# LATEST_DESIGN.net
KiCad netlist of a schematic drawn in EAGLE
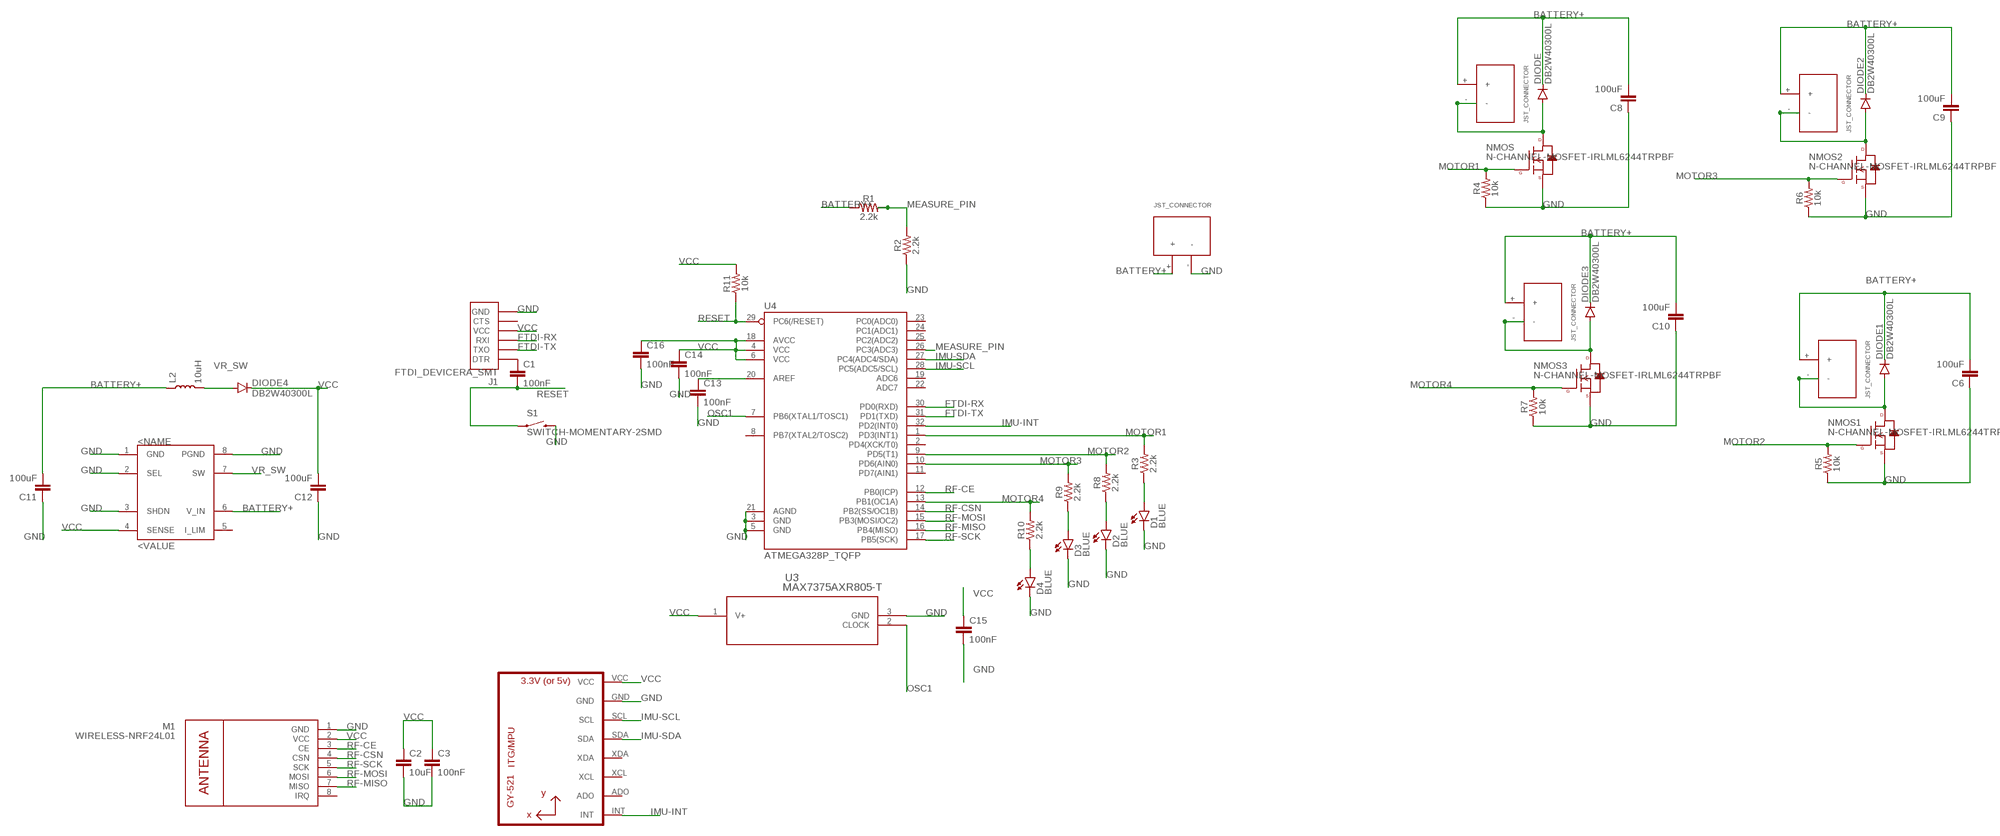
[diagram p0: schematic, sheet 1]

(export (version "E")
  (design (tool "Eeschema 10.0.6"))
  (components
    (comp (ref "C1")
      (value "100nF")
      (footprint "eagle-import:0603-CAP")
      (libsource (lib "eagle-import") (part "0.1UF-25V(+80/-20%)(0603)"))
    )
    (comp (ref "C2")
      (value "10uF")
      (footprint "eagle-import:0603-CAP")
      (libsource (lib "eagle-import") (part "CAP0603-CAP"))
    )
    (comp (ref "C3")
      (value "100nF")
      (footprint "eagle-import:0603-CAP")
      (libsource (lib "eagle-import") (part "CAP0603-CAP"))
    )
    (comp (ref "C6")
      (value "100uF")
      (footprint "eagle-import:1206")
      (libsource (lib "eagle-import") (part "CAP1206"))
    )
    (comp (ref "C8")
      (value "100uF")
      (footprint "eagle-import:1206")
      (libsource (lib "eagle-import") (part "CAP1206"))
    )
    (comp (ref "C9")
      (value "100uF")
      (footprint "eagle-import:1206")
      (libsource (lib "eagle-import") (part "CAP1206"))
    )
    (comp (ref "C10")
      (value "100uF")
      (footprint "eagle-import:1206")
      (libsource (lib "eagle-import") (part "CAP1206"))
    )
    (comp (ref "C11")
      (value "100uF")
      (footprint "eagle-import:1206")
      (libsource (lib "eagle-import") (part "CAP1206"))
    )
    (comp (ref "C12")
      (value "100uF")
      (footprint "eagle-import:1206")
      (libsource (lib "eagle-import") (part "CAP1206"))
    )
    (comp (ref "C13")
      (value "100nF")
      (footprint "eagle-import:0603-CAP")
      (libsource (lib "eagle-import") (part "CAP0603-CAP"))
    )
    (comp (ref "C14")
      (value "100nF")
      (footprint "eagle-import:0603-CAP")
      (libsource (lib "eagle-import") (part "CAP0603-CAP"))
    )
    (comp (ref "C15")
      (value "100nF")
      (footprint "eagle-import:0603-CAP")
      (libsource (lib "eagle-import") (part "0.1UF-25V(+80/-20%)(0603)"))
    )
    (comp (ref "C16")
      (value "100nF")
      (footprint "eagle-import:0603-CAP")
      (libsource (lib "eagle-import") (part "CAP0603-CAP"))
    )
    (comp (ref "D1")
      (value "BLUE")
      (footprint "eagle-import:LED-0603")
      (fields (field (name "SPICEPREFIX") "D"))
      (libsource (lib "eagle-import") (part "LED-BLUE0603"))
    )
    (comp (ref "D2")
      (value "BLUE")
      (footprint "eagle-import:LED-0603")
      (libsource (lib "eagle-import") (part "LED-BLUE0603"))
    )
    (comp (ref "D3")
      (value "BLUE")
      (footprint "eagle-import:LED-0603")
      (libsource (lib "eagle-import") (part "LED-BLUE0603"))
    )
    (comp (ref "D4")
      (value "BLUE")
      (footprint "eagle-import:LED-0603")
      (libsource (lib "eagle-import") (part "LED-BLUE0603"))
    )
    (comp (ref "DIODE")
      (value "DB2W40300L")
      (footprint "eagle-import:MINI2-F3-B")
      (libsource (lib "eagle-import") (part "DB2W40300L"))
    )
    (comp (ref "DIODE1")
      (value "DB2W40300L")
      (footprint "eagle-import:MINI2-F3-B")
      (libsource (lib "eagle-import") (part "DB2W40300L"))
    )
    (comp (ref "DIODE2")
      (value "DB2W40300L")
      (footprint "eagle-import:MINI2-F3-B")
      (libsource (lib "eagle-import") (part "DB2W40300L"))
    )
    (comp (ref "DIODE3")
      (value "DB2W40300L")
      (footprint "eagle-import:MINI2-F3-B")
      (libsource (lib "eagle-import") (part "DB2W40300L"))
    )
    (comp (ref "DIODE4")
      (value "DB2W40300L")
      (footprint "eagle-import:MINI2-F3-B")
      (libsource (lib "eagle-import") (part "DB2W40300L"))
    )
    (comp (ref "J1")
      (value "FTDI_DEVICERA_SMT")
      (footprint "eagle-import:FTDI_DEVICE_RA_SMT")
      (libsource (lib "eagle-import") (part "FTDI_DEVICERA_SMT"))
    )
    (comp (ref "L2")
      (value "10uH")
      (footprint "eagle-import:0603")
      (libsource (lib "eagle-import") (part "INDUCTOR-0603-33NH"))
    )
    (comp (ref "M1")
      (value "WIRELESS-NRF24L01")
      (footprint "eagle-import:WIRELESS-NRF24L01")
      (libsource (lib "eagle-import") (part "WIRELESS-NRF24L01"))
    )
    (comp (ref "MOTOR")
      (value "JST_CONNECTOR_FEMALE")
      (footprint "eagle-import:JST_CONNECTOR_FEMALE")
      (libsource (lib "eagle-import") (part "JST_CONNECTOR_FEMALE"))
    )
    (comp (ref "MOTOR1")
      (value "JST_CONNECTOR_FEMALE")
      (footprint "eagle-import:JST_CONNECTOR_FEMALE")
      (libsource (lib "eagle-import") (part "JST_CONNECTOR_FEMALE"))
    )
    (comp (ref "MOTOR2")
      (value "JST_CONNECTOR_FEMALE")
      (footprint "eagle-import:JST_CONNECTOR_FEMALE")
      (libsource (lib "eagle-import") (part "JST_CONNECTOR_FEMALE"))
    )
    (comp (ref "MOTOR3")
      (value "JST_CONNECTOR_FEMALE")
      (footprint "eagle-import:JST_CONNECTOR_FEMALE")
      (libsource (lib "eagle-import") (part "JST_CONNECTOR_FEMALE"))
    )
    (comp (ref "NMOS")
      (value "N-CHANNEL-MOSFET-IRLML6244TRPBF")
      (footprint "eagle-import:SOT23-3")
      (libsource (lib "eagle-import") (part "N-CHANNEL-MOSFET-IRLML6244TRPBF"))
    )
    (comp (ref "NMOS1")
      (value "N-CHANNEL-MOSFET-IRLML6244TRPBF")
      (footprint "eagle-import:SOT23-3")
      (libsource (lib "eagle-import") (part "N-CHANNEL-MOSFET-IRLML6244TRPBF"))
    )
    (comp (ref "NMOS2")
      (value "N-CHANNEL-MOSFET-IRLML6244TRPBF")
      (footprint "eagle-import:SOT23-3")
      (libsource (lib "eagle-import") (part "N-CHANNEL-MOSFET-IRLML6244TRPBF"))
    )
    (comp (ref "NMOS3")
      (value "N-CHANNEL-MOSFET-IRLML6244TRPBF")
      (footprint "eagle-import:SOT23-3")
      (libsource (lib "eagle-import") (part "N-CHANNEL-MOSFET-IRLML6244TRPBF"))
    )
    (comp (ref "R1")
      (value "2.2k")
      (footprint "eagle-import:0603")
      (libsource (lib "eagle-import") (part "2.2KOHM-0603-1/10W-1%"))
    )
    (comp (ref "R2")
      (value "2.2k")
      (footprint "eagle-import:0603")
      (libsource (lib "eagle-import") (part "2.2KOHM-0603-1/10W-1%"))
    )
    (comp (ref "R3")
      (value "2.2k")
      (footprint "eagle-import:0603")
      (fields (field (name "SPICEPREFIX") "R"))
      (libsource (lib "eagle-import") (part "2.2KOHM-0603-1/10W-1%"))
    )
    (comp (ref "R4")
      (value "10k")
      (footprint "eagle-import:0603")
      (libsource (lib "eagle-import") (part "2.2KOHM-0603-1/10W-1%"))
    )
    (comp (ref "R5")
      (value "10k")
      (footprint "eagle-import:0603")
      (libsource (lib "eagle-import") (part "2.2KOHM-0603-1/10W-1%"))
    )
    (comp (ref "R6")
      (value "10k")
      (footprint "eagle-import:0603")
      (libsource (lib "eagle-import") (part "2.2KOHM-0603-1/10W-1%"))
    )
    (comp (ref "R7")
      (value "10k")
      (footprint "eagle-import:0603")
      (libsource (lib "eagle-import") (part "2.2KOHM-0603-1/10W-1%"))
    )
    (comp (ref "R8")
      (value "2.2k")
      (footprint "eagle-import:0603")
      (libsource (lib "eagle-import") (part "2.2KOHM-0603-1/10W-1%"))
    )
    (comp (ref "R9")
      (value "2.2k")
      (footprint "eagle-import:0603")
      (libsource (lib "eagle-import") (part "2.2KOHM-0603-1/10W-1%"))
    )
    (comp (ref "R10")
      (value "2.2k")
      (footprint "eagle-import:0603")
      (libsource (lib "eagle-import") (part "2.2KOHM-0603-1/10W-1%"))
    )
    (comp (ref "R11")
      (value "10k")
      (footprint "eagle-import:0603")
      (libsource (lib "eagle-import") (part "2.2KOHM-0603-1/10W-1%"))
    )
    (comp (ref "S1")
      (value "SWITCH-MOMENTARY-2SMD")
      (footprint "eagle-import:TACTILE-SWITCH-SMD")
      (libsource (lib "eagle-import") (part "SWITCH-MOMENTARY-2SMD"))
    )
    (comp (ref "U$1")
      (value "JST_CONNECTOR_FEMALE")
      (footprint "eagle-import:JST_CONNECTOR_FEMALE")
      (libsource (lib "eagle-import") (part "JST_CONNECTOR_FEMALE"))
    )
    (comp (ref "U$4")
      (value "LT1300CS8#PBF-NDLT1300CS8#PBF-ND")
      (footprint "eagle-import:SOIC-8_S")
      (libsource (lib "eagle-import") (part "LT1300CS8#PBF-NDLT1300CS8#PBF-ND"))
    )
    (comp (ref "U2")
      (value "GY-521MPU6050")
      (footprint "eagle-import:GY-521")
      (libsource (lib "eagle-import") (part "GY-521MPU6050"))
    )
    (comp (ref "U3")
      (value "MAX7375AXR805-T")
      (footprint "eagle-import:21-0075D")
      (fields (field (name "MF") "Maxim Integrated") (field (name "MP") "MAX7375AXR805+T"))
      (libsource (lib "eagle-import") (part "MAX7375AXR805-T"))
    )
    (comp (ref "U4")
      (value "ATMEGA328P_TQFP")
      (footprint "eagle-import:TQFP32-08")
      (libsource (lib "eagle-import") (part "ATMEGA328P_TQFP"))
    )
  )
  (nets
    (net (code "1") (name "BATTERY+") (class "Default")
      (node (ref "C10") (pin "2") (pinfunction "2_2") (pintype "passive"))
      (node (ref "C11") (pin "2") (pinfunction "2_2") (pintype "passive"))
      (node (ref "C6") (pin "2") (pinfunction "2_2") (pintype "passive"))
      (node (ref "C8") (pin "2") (pinfunction "2_2") (pintype "passive"))
      (node (ref "C9") (pin "2") (pinfunction "2_2") (pintype "passive"))
      (node (ref "DIODE") (pin "NEG") (pinfunction "GPIN_NEG") (pintype "passive"))
      (node (ref "DIODE1") (pin "NEG") (pinfunction "GPIN_NEG") (pintype "passive"))
      (node (ref "DIODE2") (pin "NEG") (pinfunction "GPIN_NEG") (pintype "passive"))
      (node (ref "DIODE3") (pin "NEG") (pinfunction "GPIN_NEG") (pintype "passive"))
      (node (ref "L2") (pin "1") (pinfunction "1_1") (pintype "passive"))
      (node (ref "MOTOR") (pin "+") (pinfunction "+_+") (pintype "bidirectional"))
      (node (ref "MOTOR1") (pin "+") (pinfunction "+_+") (pintype "bidirectional"))
      (node (ref "MOTOR2") (pin "+") (pinfunction "+_+") (pintype "bidirectional"))
      (node (ref "MOTOR3") (pin "+") (pinfunction "+_+") (pintype "bidirectional"))
      (node (ref "R1") (pin "1") (pinfunction "1_1") (pintype "passive"))
      (node (ref "U$1") (pin "+") (pinfunction "+_+") (pintype "bidirectional"))
      (node (ref "U$4") (pin "6") (pinfunction "V_IN_6") (pintype "bidirectional"))
    )
    (net (code "2") (name "FTDI-RX") (class "Default")
      (node (ref "J1") (pin "3") (pinfunction "RXI_3") (pintype "bidirectional"))
      (node (ref "U4") (pin "30") (pinfunction "PD0(RXD)_30") (pintype "bidirectional"))
    )
    (net (code "3") (name "FTDI-TX") (class "Default")
      (node (ref "J1") (pin "2") (pinfunction "TXO_2") (pintype "bidirectional"))
      (node (ref "U4") (pin "31") (pinfunction "PD1(TXD)_31") (pintype "bidirectional"))
    )
    (net (code "4") (name "GND") (class "Default")
      (node (ref "C10") (pin "1") (pinfunction "1_1") (pintype "passive"))
      (node (ref "C11") (pin "1") (pinfunction "1_1") (pintype "passive"))
      (node (ref "C12") (pin "1") (pinfunction "1_1") (pintype "passive"))
      (node (ref "C13") (pin "2") (pinfunction "2_2") (pintype "passive"))
      (node (ref "C14") (pin "2") (pinfunction "2_2") (pintype "passive"))
      (node (ref "C15") (pin "2") (pinfunction "2_2") (pintype "passive"))
      (node (ref "C16") (pin "2") (pinfunction "2_2") (pintype "passive"))
      (node (ref "C2") (pin "2") (pinfunction "2_2") (pintype "passive"))
      (node (ref "C3") (pin "2") (pinfunction "2_2") (pintype "passive"))
      (node (ref "C6") (pin "1") (pinfunction "1_1") (pintype "passive"))
      (node (ref "C8") (pin "1") (pinfunction "1_1") (pintype "passive"))
      (node (ref "C9") (pin "1") (pinfunction "1_1") (pintype "passive"))
      (node (ref "D1") (pin "C") (pinfunction "C_C") (pintype "passive"))
      (node (ref "D2") (pin "C") (pinfunction "C_C") (pintype "passive"))
      (node (ref "D3") (pin "C") (pinfunction "C_C") (pintype "passive"))
      (node (ref "D4") (pin "C") (pinfunction "C_C") (pintype "passive"))
      (node (ref "J1") (pin "6") (pinfunction "GND_6") (pintype "bidirectional"))
      (node (ref "M1") (pin "1") (pinfunction "GND_1") (pintype "power_in"))
      (node (ref "NMOS") (pin "2") (pinfunction "S_2") (pintype "passive"))
      (node (ref "NMOS1") (pin "2") (pinfunction "S_2") (pintype "passive"))
      (node (ref "NMOS2") (pin "2") (pinfunction "S_2") (pintype "passive"))
      (node (ref "NMOS3") (pin "2") (pinfunction "S_2") (pintype "passive"))
      (node (ref "R2") (pin "1") (pinfunction "1_1") (pintype "passive"))
      (node (ref "R4") (pin "1") (pinfunction "1_1") (pintype "passive"))
      (node (ref "R5") (pin "1") (pinfunction "1_1") (pintype "passive"))
      (node (ref "R6") (pin "1") (pinfunction "1_1") (pintype "passive"))
      (node (ref "R7") (pin "1") (pinfunction "1_1") (pintype "passive"))
      (node (ref "S1") (pin "3") (pinfunction "2_3") (pintype "passive"))
      (node (ref "U$1") (pin "-") (pinfunction "-_-") (pintype "bidirectional"))
      (node (ref "U$4") (pin "1") (pinfunction "GND_1") (pintype "bidirectional"))
      (node (ref "U$4") (pin "2") (pinfunction "SEL_2") (pintype "bidirectional"))
      (node (ref "U$4") (pin "3") (pinfunction "SHDN_3") (pintype "bidirectional"))
      (node (ref "U$4") (pin "8") (pinfunction "PGND_8") (pintype "bidirectional"))
      (node (ref "U2") (pin "GND") (pinfunction "GND_GND") (pintype "bidirectional"))
      (node (ref "U3") (pin "3") (pinfunction "GND_3") (pintype "power_in"))
      (node (ref "U4") (pin "21") (pinfunction "AGND_21") (pintype "bidirectional"))
      (node (ref "U4") (pin "3") (pinfunction "GND_3") (pintype "bidirectional"))
      (node (ref "U4") (pin "5") (pinfunction "GND_5") (pintype "bidirectional"))
    )
    (net (code "5") (name "IMU-INT") (class "Default")
      (node (ref "U2") (pin "INT") (pinfunction "INT_INT") (pintype "bidirectional"))
      (node (ref "U4") (pin "32") (pinfunction "PD2(INT0)_32") (pintype "bidirectional"))
    )
    (net (code "6") (name "IMU-SCL") (class "Default")
      (node (ref "U2") (pin "SCL") (pinfunction "SCL_SCL") (pintype "bidirectional"))
      (node (ref "U4") (pin "28") (pinfunction "PC5(ADC5/SCL)_28") (pintype "bidirectional"))
    )
    (net (code "7") (name "IMU-SDA") (class "Default")
      (node (ref "U2") (pin "SDA") (pinfunction "SDA_SDA") (pintype "bidirectional"))
      (node (ref "U4") (pin "27") (pinfunction "PC4(ADC4/SDA)_27") (pintype "bidirectional"))
    )
    (net (code "8") (name "MEASURE_PIN") (class "Default")
      (node (ref "R1") (pin "2") (pinfunction "2_2") (pintype "passive"))
      (node (ref "R2") (pin "2") (pinfunction "2_2") (pintype "passive"))
      (node (ref "U4") (pin "26") (pinfunction "PC3(ADC3)_26") (pintype "bidirectional"))
    )
    (net (code "9") (name "MOTOR1") (class "Default")
      (node (ref "NMOS") (pin "1") (pinfunction "G_1") (pintype "passive"))
      (node (ref "R3") (pin "2") (pinfunction "2_2") (pintype "passive"))
      (node (ref "R4") (pin "2") (pinfunction "2_2") (pintype "passive"))
      (node (ref "U4") (pin "1") (pinfunction "PD3(INT1)_1") (pintype "bidirectional"))
    )
    (net (code "10") (name "MOTOR2") (class "Default")
      (node (ref "NMOS1") (pin "1") (pinfunction "G_1") (pintype "passive"))
      (node (ref "R5") (pin "2") (pinfunction "2_2") (pintype "passive"))
      (node (ref "R8") (pin "2") (pinfunction "2_2") (pintype "passive"))
      (node (ref "U4") (pin "9") (pinfunction "PD5(T1)_9") (pintype "bidirectional"))
    )
    (net (code "11") (name "MOTOR3") (class "Default")
      (node (ref "NMOS2") (pin "1") (pinfunction "G_1") (pintype "passive"))
      (node (ref "R6") (pin "2") (pinfunction "2_2") (pintype "passive"))
      (node (ref "R9") (pin "2") (pinfunction "2_2") (pintype "passive"))
      (node (ref "U4") (pin "10") (pinfunction "PD6(AIN0)_10") (pintype "bidirectional"))
    )
    (net (code "12") (name "MOTOR4") (class "Default")
      (node (ref "NMOS3") (pin "1") (pinfunction "G_1") (pintype "passive"))
      (node (ref "R10") (pin "2") (pinfunction "2_2") (pintype "passive"))
      (node (ref "R7") (pin "2") (pinfunction "2_2") (pintype "passive"))
      (node (ref "U4") (pin "13") (pinfunction "PB1(OC1A)_13") (pintype "bidirectional"))
    )
    (net (code "13") (name "Net-(D1-PadA)") (class "Default")
      (node (ref "D1") (pin "A") (pinfunction "A_A") (pintype "passive"))
      (node (ref "R3") (pin "1") (pinfunction "1_1") (pintype "passive"))
    )
    (net (code "14") (name "Net-(D2-PadA)") (class "Default")
      (node (ref "D2") (pin "A") (pinfunction "A_A") (pintype "passive"))
      (node (ref "R8") (pin "1") (pinfunction "1_1") (pintype "passive"))
    )
    (net (code "15") (name "Net-(D3-PadA)") (class "Default")
      (node (ref "D3") (pin "A") (pinfunction "A_A") (pintype "passive"))
      (node (ref "R9") (pin "1") (pinfunction "1_1") (pintype "passive"))
    )
    (net (code "16") (name "Net-(D4-PadA)") (class "Default")
      (node (ref "D4") (pin "A") (pinfunction "A_A") (pintype "passive"))
      (node (ref "R10") (pin "1") (pinfunction "1_1") (pintype "passive"))
    )
    (net (code "17") (name "Net-(DIODE-PPIN)") (class "Default")
      (node (ref "DIODE") (pin "POS") (pinfunction "PPIN_POS") (pintype "passive"))
      (node (ref "MOTOR") (pin "-") (pinfunction "-_-") (pintype "bidirectional"))
      (node (ref "NMOS") (pin "3") (pinfunction "D_3") (pintype "passive"))
    )
    (net (code "18") (name "Net-(DIODE1-PPIN)") (class "Default")
      (node (ref "DIODE1") (pin "POS") (pinfunction "PPIN_POS") (pintype "passive"))
      (node (ref "MOTOR1") (pin "-") (pinfunction "-_-") (pintype "bidirectional"))
      (node (ref "NMOS1") (pin "3") (pinfunction "D_3") (pintype "passive"))
    )
    (net (code "19") (name "Net-(DIODE2-PPIN)") (class "Default")
      (node (ref "DIODE2") (pin "POS") (pinfunction "PPIN_POS") (pintype "passive"))
      (node (ref "MOTOR2") (pin "-") (pinfunction "-_-") (pintype "bidirectional"))
      (node (ref "NMOS2") (pin "3") (pinfunction "D_3") (pintype "passive"))
    )
    (net (code "20") (name "Net-(DIODE3-PPIN)") (class "Default")
      (node (ref "DIODE3") (pin "POS") (pinfunction "PPIN_POS") (pintype "passive"))
      (node (ref "MOTOR3") (pin "-") (pinfunction "-_-") (pintype "bidirectional"))
      (node (ref "NMOS3") (pin "3") (pinfunction "D_3") (pintype "passive"))
    )
    (net (code "21") (name "Net-(J1-DTR)") (class "Default")
      (node (ref "C1") (pin "1") (pinfunction "1_1") (pintype "passive"))
      (node (ref "J1") (pin "1") (pinfunction "DTR_1") (pintype "bidirectional"))
    )
    (net (code "22") (name "Net-(U4-AREF)") (class "Default")
      (node (ref "C13") (pin "1") (pinfunction "1_1") (pintype "passive"))
      (node (ref "U4") (pin "20") (pinfunction "AREF_20") (pintype "bidirectional"))
    )
    (net (code "23") (name "OSC1") (class "Default")
      (node (ref "U3") (pin "2") (pinfunction "CLOCK_2") (pintype "output"))
      (node (ref "U4") (pin "7") (pinfunction "PB6(XTAL1/TOSC1)_7") (pintype "bidirectional"))
    )
    (net (code "24") (name "RESET") (class "Default")
      (node (ref "C1") (pin "2") (pinfunction "2_2") (pintype "passive"))
      (node (ref "R11") (pin "1") (pinfunction "1_1") (pintype "passive"))
      (node (ref "S1") (pin "1") (pinfunction "1_1") (pintype "passive"))
      (node (ref "U4") (pin "29") (pinfunction "PC6(/RESET)_29") (pintype "bidirectional"))
    )
    (net (code "25") (name "RF-CE") (class "Default")
      (node (ref "M1") (pin "3") (pinfunction "CE_3") (pintype "bidirectional"))
      (node (ref "U4") (pin "12") (pinfunction "PB0(ICP)_12") (pintype "bidirectional"))
    )
    (net (code "26") (name "RF-CSN") (class "Default")
      (node (ref "M1") (pin "4") (pinfunction "CSN_4") (pintype "bidirectional"))
      (node (ref "U4") (pin "14") (pinfunction "PB2(SS/OC1B)_14") (pintype "bidirectional"))
    )
    (net (code "27") (name "RF-MISO") (class "Default")
      (node (ref "M1") (pin "7") (pinfunction "MISO_7") (pintype "bidirectional"))
      (node (ref "U4") (pin "16") (pinfunction "PB4(MISO)_16") (pintype "bidirectional"))
    )
    (net (code "28") (name "RF-MOSI") (class "Default")
      (node (ref "M1") (pin "6") (pinfunction "MOSI_6") (pintype "bidirectional"))
      (node (ref "U4") (pin "15") (pinfunction "PB3(MOSI/OC2)_15") (pintype "bidirectional"))
    )
    (net (code "29") (name "RF-SCK") (class "Default")
      (node (ref "M1") (pin "5") (pinfunction "SCK_5") (pintype "bidirectional"))
      (node (ref "U4") (pin "17") (pinfunction "PB5(SCK)_17") (pintype "bidirectional"))
    )
    (net (code "30") (name "VCC") (class "Default")
      (node (ref "C12") (pin "2") (pinfunction "2_2") (pintype "passive"))
      (node (ref "C14") (pin "1") (pinfunction "1_1") (pintype "passive"))
      (node (ref "C15") (pin "1") (pinfunction "1_1") (pintype "passive"))
      (node (ref "C16") (pin "1") (pinfunction "1_1") (pintype "passive"))
      (node (ref "C2") (pin "1") (pinfunction "1_1") (pintype "passive"))
      (node (ref "C3") (pin "1") (pinfunction "1_1") (pintype "passive"))
      (node (ref "DIODE4") (pin "NEG") (pinfunction "GPIN_NEG") (pintype "passive"))
      (node (ref "J1") (pin "4") (pinfunction "VCC_4") (pintype "bidirectional"))
      (node (ref "M1") (pin "2") (pinfunction "VCC_2") (pintype "power_in"))
      (node (ref "R11") (pin "2") (pinfunction "2_2") (pintype "passive"))
      (node (ref "U$4") (pin "4") (pinfunction "SENSE_4") (pintype "bidirectional"))
      (node (ref "U2") (pin "VCC") (pinfunction "VCC_VCC") (pintype "bidirectional"))
      (node (ref "U3") (pin "1") (pinfunction "V+_1") (pintype "power_in"))
      (node (ref "U4") (pin "18") (pinfunction "AVCC_18") (pintype "bidirectional"))
      (node (ref "U4") (pin "4") (pinfunction "VCC_4") (pintype "bidirectional"))
      (node (ref "U4") (pin "6") (pinfunction "VCC_6") (pintype "bidirectional"))
    )
    (net (code "31") (name "VR_SW") (class "Default")
      (node (ref "DIODE4") (pin "POS") (pinfunction "PPIN_POS") (pintype "passive"))
      (node (ref "L2") (pin "2") (pinfunction "2_2") (pintype "passive"))
      (node (ref "U$4") (pin "7") (pinfunction "SW_7") (pintype "bidirectional"))
    )
    (net (code "32") (name "unconnected-(J1-CTS-Pad5)") (class "Default")
      (node (ref "J1") (pin "5") (pinfunction "CTS_5") (pintype "bidirectional"))
    )
    (net (code "33") (name "unconnected-(M1-IRQ-Pad8)") (class "Default")
      (node (ref "M1") (pin "8") (pinfunction "IRQ_8") (pintype "bidirectional"))
    )
    (net (code "34") (name "unconnected-(U$4-I_LIM-Pad5)") (class "Default")
      (node (ref "U$4") (pin "5") (pinfunction "I_LIM_5") (pintype "bidirectional"))
    )
    (net (code "35") (name "unconnected-(U2-PadADO)") (class "Default")
      (node (ref "U2") (pin "ADO") (pinfunction "ADO_ADO") (pintype "bidirectional"))
    )
    (net (code "36") (name "unconnected-(U2-PadXCL)") (class "Default")
      (node (ref "U2") (pin "XCL") (pinfunction "XCL_XCL") (pintype "bidirectional"))
    )
    (net (code "37") (name "unconnected-(U2-PadXDA)") (class "Default")
      (node (ref "U2") (pin "XDA") (pinfunction "XDA_XDA") (pintype "bidirectional"))
    )
    (net (code "38") (name "unconnected-(U4-ADC6-Pad19)") (class "Default")
      (node (ref "U4") (pin "19") (pinfunction "ADC6_19") (pintype "bidirectional"))
    )
    (net (code "39") (name "unconnected-(U4-ADC7-Pad22)") (class "Default")
      (node (ref "U4") (pin "22") (pinfunction "ADC7_22") (pintype "bidirectional"))
    )
    (net (code "40") (name "unconnected-(U4-PB7(XTAL2{slash}TOSC2)-Pad8)") (class "Default")
      (node (ref "U4") (pin "8") (pinfunction "PB7(XTAL2/TOSC2)_8") (pintype "bidirectional"))
    )
    (net (code "41") (name "unconnected-(U4-PC0(ADC0)-Pad23)") (class "Default")
      (node (ref "U4") (pin "23") (pinfunction "PC0(ADC0)_23") (pintype "bidirectional"))
    )
    (net (code "42") (name "unconnected-(U4-PC1(ADC1)-Pad24)") (class "Default")
      (node (ref "U4") (pin "24") (pinfunction "PC1(ADC1)_24") (pintype "bidirectional"))
    )
    (net (code "43") (name "unconnected-(U4-PC2(ADC2)-Pad25)") (class "Default")
      (node (ref "U4") (pin "25") (pinfunction "PC2(ADC2)_25") (pintype "bidirectional"))
    )
    (net (code "44") (name "unconnected-(U4-PD4(XCK{slash}T0)-Pad2)") (class "Default")
      (node (ref "U4") (pin "2") (pinfunction "PD4(XCK/T0)_2") (pintype "bidirectional"))
    )
    (net (code "45") (name "unconnected-(U4-PD7(AIN1)-Pad11)") (class "Default")
      (node (ref "U4") (pin "11") (pinfunction "PD7(AIN1)_11") (pintype "bidirectional"))
    )
  )
)
